# llrf_afe_dds_channel.net
KiCad netlist of a schematic drawn in Altium Designer
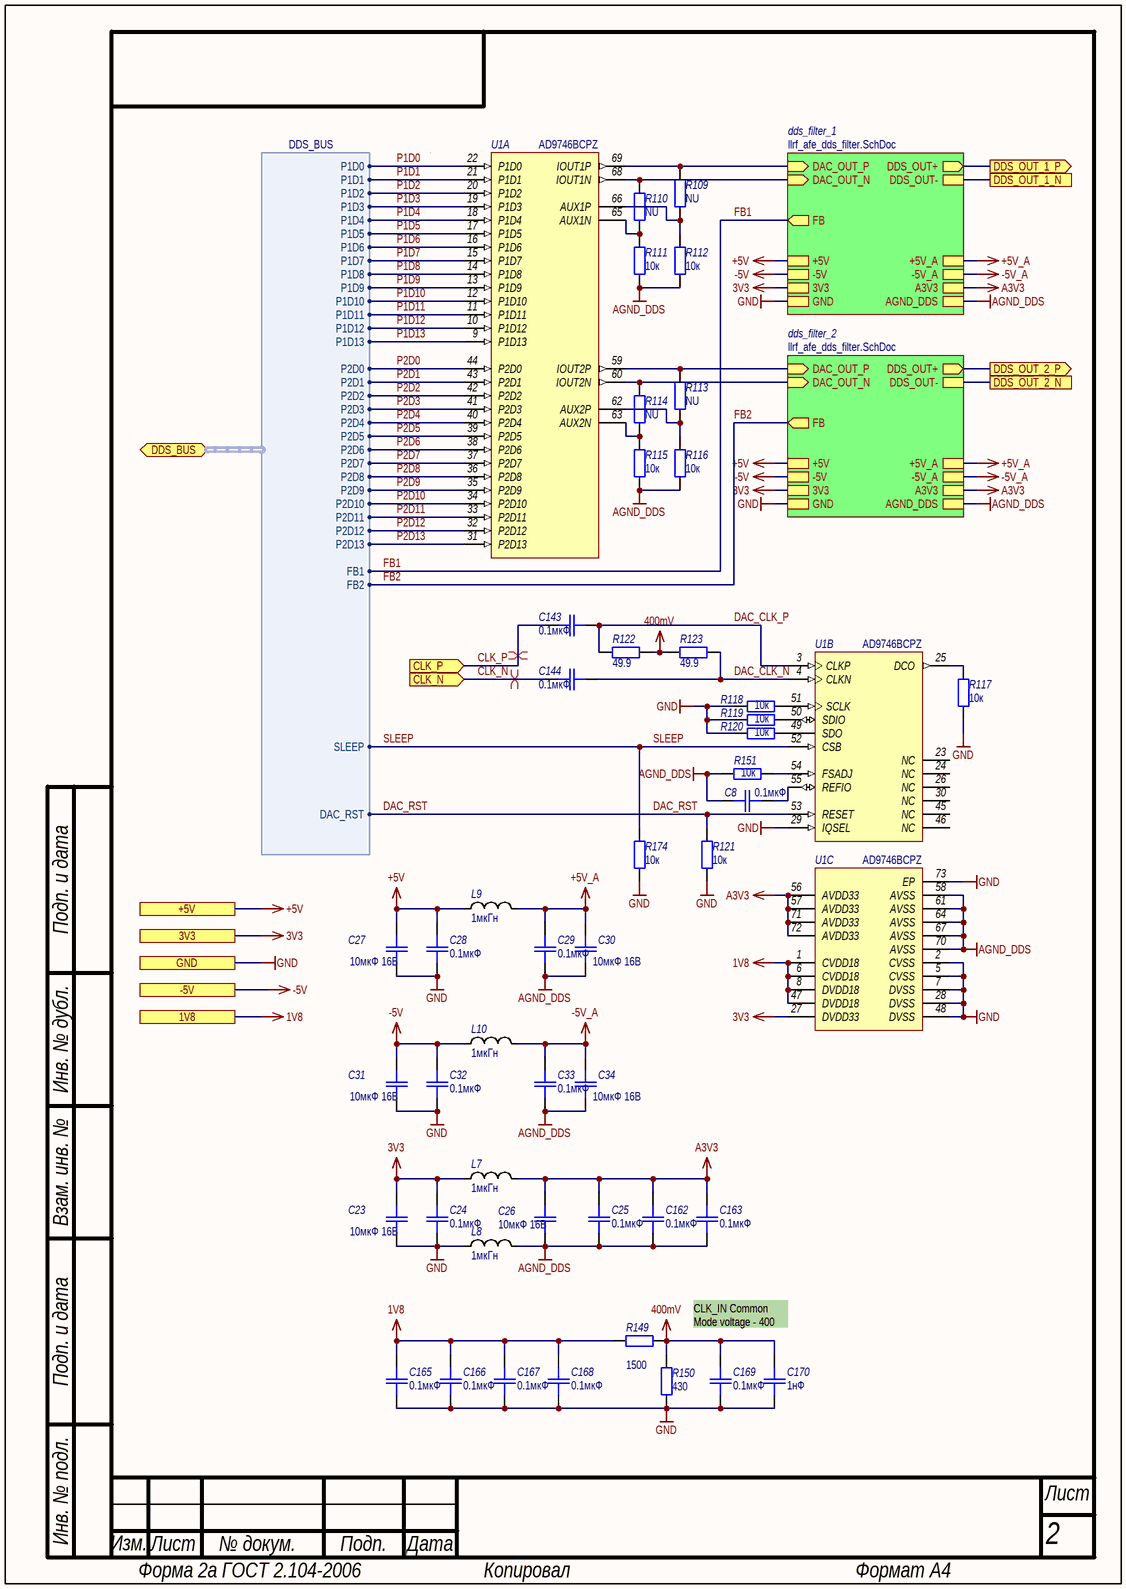
[diagram p0: llrf_afe_dds_channel.SchDoc]

(export (version "E")
  (design (tool "Eeschema 10.0.6"))
  (components
    (comp (ref "C8")
      (value "0.1мкФ")
      (footprint "SMD_C0402")
      (description "Capacitor")
      (libsource (lib "Passive") (part "Capacitor"))
    )
    (comp (ref "C23")
      (value "10мкФ 16В")
      (footprint "SMD_C0603")
      (description "Capacitor")
      (libsource (lib "Passive") (part "Capacitor"))
    )
    (comp (ref "C24")
      (value "0.1мкФ")
      (footprint "SMD_C0402")
      (description "Capacitor")
      (libsource (lib "Passive") (part "Capacitor"))
    )
    (comp (ref "C25")
      (value "0.1мкФ")
      (footprint "SMD_C0402")
      (description "Capacitor")
      (libsource (lib "Passive") (part "Capacitor"))
    )
    (comp (ref "C26")
      (value "10мкФ 16В")
      (footprint "SMD_C0603")
      (description "Capacitor")
      (libsource (lib "Passive") (part "Capacitor"))
    )
    (comp (ref "C27")
      (value "10мкФ 16В")
      (footprint "SMD_C0603")
      (description "Capacitor")
      (libsource (lib "Passive") (part "Capacitor"))
    )
    (comp (ref "C28")
      (value "0.1мкФ")
      (footprint "SMD_C0402")
      (description "Capacitor")
      (libsource (lib "Passive") (part "Capacitor"))
    )
    (comp (ref "C29")
      (value "0.1мкФ")
      (footprint "SMD_C0402")
      (description "Capacitor")
      (libsource (lib "Passive") (part "Capacitor"))
    )
    (comp (ref "C30")
      (value "10мкФ 16В")
      (footprint "SMD_C0603")
      (description "Capacitor")
      (libsource (lib "Passive") (part "Capacitor"))
    )
    (comp (ref "C31")
      (value "10мкФ 16В")
      (footprint "SMD_C0603")
      (description "Capacitor")
      (libsource (lib "Passive") (part "Capacitor"))
    )
    (comp (ref "C32")
      (value "0.1мкФ")
      (footprint "SMD_C0402")
      (description "Capacitor")
      (libsource (lib "Passive") (part "Capacitor"))
    )
    (comp (ref "C33")
      (value "0.1мкФ")
      (footprint "SMD_C0402")
      (description "Capacitor")
      (libsource (lib "Passive") (part "Capacitor"))
    )
    (comp (ref "C34")
      (value "10мкФ 16В")
      (footprint "SMD_C0603")
      (description "Capacitor")
      (libsource (lib "Passive") (part "Capacitor"))
    )
    (comp (ref "C143")
      (value "0.1мкФ")
      (footprint "SMD_C0402")
      (description "Capacitor")
      (libsource (lib "Passive") (part "Capacitor"))
    )
    (comp (ref "C144")
      (value "0.1мкФ")
      (footprint "SMD_C0402")
      (description "Capacitor")
      (libsource (lib "Passive") (part "Capacitor"))
    )
    (comp (ref "C162")
      (value "0.1мкФ")
      (footprint "SMD_C0402")
      (description "Capacitor")
      (libsource (lib "Passive") (part "Capacitor"))
    )
    (comp (ref "C163")
      (value "0.1мкФ")
      (footprint "SMD_C0402")
      (description "Capacitor")
      (libsource (lib "Passive") (part "Capacitor"))
    )
    (comp (ref "C165")
      (value "0.1мкФ")
      (footprint "SMD_C0402")
      (description "Capacitor")
      (libsource (lib "Passive") (part "Capacitor"))
    )
    (comp (ref "C166")
      (value "0.1мкФ")
      (footprint "SMD_C0402")
      (description "Capacitor")
      (libsource (lib "Passive") (part "Capacitor"))
    )
    (comp (ref "C167")
      (value "0.1мкФ")
      (footprint "SMD_C0402")
      (description "Capacitor")
      (libsource (lib "Passive") (part "Capacitor"))
    )
    (comp (ref "C168")
      (value "0.1мкФ")
      (footprint "SMD_C0402")
      (description "Capacitor")
      (libsource (lib "Passive") (part "Capacitor"))
    )
    (comp (ref "C169")
      (value "0.1мкФ")
      (footprint "SMD_C0402")
      (description "Capacitor")
      (libsource (lib "Passive") (part "Capacitor"))
    )
    (comp (ref "C170")
      (value "1нФ")
      (footprint "SMD_C0402")
      (description "Capacitor")
      (libsource (lib "Passive") (part "Capacitor"))
    )
    (comp (ref "L7")
      (value "1мкГн")
      (footprint "SMD_0805")
      (description "Inductor")
      (libsource (lib "Passive") (part "Inductor"))
    )
    (comp (ref "L8")
      (value "1мкГн")
      (footprint "SMD_0805")
      (description "Inductor")
      (libsource (lib "Passive") (part "Inductor"))
    )
    (comp (ref "L9")
      (value "1мкГн")
      (footprint "SMD_0805")
      (description "Inductor")
      (libsource (lib "Passive") (part "Inductor"))
    )
    (comp (ref "L10")
      (value "1мкГн")
      (footprint "SMD_0805")
      (description "Inductor")
      (libsource (lib "Passive") (part "Inductor"))
    )
    (comp (ref "R109")
      (value "NU")
      (footprint "SMD_0603")
      (description "Resistor")
      (libsource (lib "") (part "Resistor_1"))
    )
    (comp (ref "R110")
      (value "NU")
      (footprint "SMD_0603")
      (description "Resistor")
      (libsource (lib "") (part "Resistor_1"))
    )
    (comp (ref "R111")
      (value "10к")
      (footprint "SMD_0603")
      (description "Resistor")
      (libsource (lib "") (part "Resistor_1"))
    )
    (comp (ref "R112")
      (value "10к")
      (footprint "SMD_0603")
      (description "Resistor")
      (libsource (lib "") (part "Resistor_1"))
    )
    (comp (ref "R113")
      (value "NU")
      (footprint "SMD_0603")
      (description "Resistor")
      (libsource (lib "") (part "Resistor_1"))
    )
    (comp (ref "R114")
      (value "NU")
      (footprint "SMD_0603")
      (description "Resistor")
      (libsource (lib "") (part "Resistor_1"))
    )
    (comp (ref "R115")
      (value "10к")
      (footprint "SMD_0603")
      (description "Resistor")
      (libsource (lib "") (part "Resistor_1"))
    )
    (comp (ref "R116")
      (value "10к")
      (footprint "SMD_0603")
      (description "Resistor")
      (libsource (lib "") (part "Resistor_1"))
    )
    (comp (ref "R117")
      (value "10к")
      (footprint "SMD_0603")
      (description "Resistor")
      (libsource (lib "Passive") (part "Resistor"))
    )
    (comp (ref "R118")
      (value "10к")
      (footprint "SMD_0603")
      (description "Resistor")
      (libsource (lib "") (part "Resistor_2"))
    )
    (comp (ref "R119")
      (value "10к")
      (footprint "SMD_0603")
      (description "Resistor")
      (libsource (lib "") (part "Resistor_2"))
    )
    (comp (ref "R120")
      (value "10к")
      (footprint "SMD_0603")
      (description "Resistor")
      (libsource (lib "") (part "Resistor_2"))
    )
    (comp (ref "R121")
      (value "10к")
      (footprint "SMD_0603")
      (description "Resistor")
      (libsource (lib "Passive") (part "Resistor"))
    )
    (comp (ref "R122")
      (value "49.9")
      (footprint "SMD_0603")
      (description "Resistor")
      (libsource (lib "") (part "Resistor_3"))
    )
    (comp (ref "R123")
      (value "49.9")
      (footprint "SMD_0603")
      (description "Resistor")
      (libsource (lib "") (part "Resistor_3"))
    )
    (comp (ref "R149")
      (value "1500")
      (footprint "SMD_0603")
      (description "Resistor")
      (libsource (lib "") (part "Resistor_3"))
    )
    (comp (ref "R150")
      (value "430")
      (footprint "SMD_0603")
      (description "Resistor")
      (libsource (lib "") (part "Resistor_1"))
    )
    (comp (ref "R151")
      (value "10к")
      (footprint "SMD_0603")
      (description "Resistor")
      (libsource (lib "") (part "Resistor_1"))
    )
    (comp (ref "R174")
      (value "10к")
      (footprint "SMD_0603")
      (description "Resistor")
      (libsource (lib "Passive") (part "Resistor"))
    )
    (comp (ref "U1")
      (value "AD9746BCPZ")
      (footprint "LFCSP-72")
      (description "Dual 14-Bit Digital-to-Analog Converter, 250 Msps, -40 to +85 degC, CP-72-1, Pb-Free, Tray")
      (fields (field (name "НАИМЕНОВАНИЕ") "AD9746BCPZ"))
      (libsource (lib "Dac") (part "AD9746BCPZ"))
    )
  )
  (nets
    (net (code "2") (name "+5V") (class "Default")
      (node (ref "C27") (pin "2") (pinfunction "2_2") (pintype "passive"))
      (node (ref "C28") (pin "2") (pinfunction "2_2") (pintype "passive"))
      (node (ref "L9") (pin "1") (pinfunction "1_1") (pintype "passive"))
    )
    (net (code "3") (name "+5V_A") (class "Default")
      (node (ref "C29") (pin "2") (pinfunction "2_2") (pintype "passive"))
      (node (ref "C30") (pin "2") (pinfunction "2_2") (pintype "passive"))
      (node (ref "L9") (pin "2") (pinfunction "2_2") (pintype "passive"))
    )
    (net (code "4") (name "-5V") (class "Default")
      (node (ref "C31") (pin "2") (pinfunction "2_2") (pintype "passive"))
      (node (ref "C32") (pin "2") (pinfunction "2_2") (pintype "passive"))
      (node (ref "L10") (pin "1") (pinfunction "1_1") (pintype "passive"))
    )
    (net (code "5") (name "-5V_A") (class "Default")
      (node (ref "C33") (pin "2") (pinfunction "2_2") (pintype "passive"))
      (node (ref "C34") (pin "2") (pinfunction "2_2") (pintype "passive"))
      (node (ref "L10") (pin "2") (pinfunction "2_2") (pintype "passive"))
    )
    (net (code "6") (name "/CLK_N") (class "Default")
      (node (ref "C144") (pin "2") (pinfunction "2_2") (pintype "passive"))
    )
    (net (code "7") (name "/CLK_P") (class "Default")
      (node (ref "C143") (pin "2") (pinfunction "2_2") (pintype "passive"))
    )
    (net (code "8") (name "/DAC_CLK_N") (class "Default")
      (node (ref "C144") (pin "1") (pinfunction "1_1") (pintype "passive"))
      (node (ref "R123") (pin "1") (pinfunction "1_1") (pintype "passive"))
      (node (ref "U1") (pin "4") (pinfunction "CLKN_4") (pintype "input"))
    )
    (net (code "9") (name "/DAC_CLK_P") (class "Default")
      (node (ref "C143") (pin "1") (pinfunction "1_1") (pintype "passive"))
      (node (ref "R122") (pin "2") (pinfunction "2_2") (pintype "passive"))
      (node (ref "U1") (pin "3") (pinfunction "CLKP_3") (pintype "input"))
    )
    (net (code "10") (name "/DAC_OUT_N") (class "Default")
      (node (ref "R110") (pin "2") (pinfunction "2_2") (pintype "passive"))
      (node (ref "U1") (pin "68") (pinfunction "IOUT1N_68") (pintype "output"))
    )
    (net (code "11") (name "/DAC_OUT_N_1") (class "Default")
      (node (ref "R114") (pin "2") (pinfunction "2_2") (pintype "passive"))
      (node (ref "U1") (pin "60") (pinfunction "IOUT2N_60") (pintype "output"))
    )
    (net (code "12") (name "/DAC_OUT_P") (class "Default")
      (node (ref "R109") (pin "2") (pinfunction "2_2") (pintype "passive"))
      (node (ref "U1") (pin "69") (pinfunction "IOUT1P_69") (pintype "output"))
    )
    (net (code "13") (name "/DAC_OUT_P_1") (class "Default")
      (node (ref "R113") (pin "2") (pinfunction "2_2") (pintype "passive"))
      (node (ref "U1") (pin "59") (pinfunction "IOUT2P_59") (pintype "output"))
    )
    (net (code "14") (name "/DAC_RST") (class "Default")
      (node (ref "R121") (pin "2") (pinfunction "2_2") (pintype "passive"))
      (node (ref "U1") (pin "53") (pinfunction "RESET_53") (pintype "input"))
    )
    (net (code "21") (name "/P1D0") (class "Default")
      (node (ref "U1") (pin "22") (pinfunction "P1D0_22") (pintype "input"))
    )
    (net (code "22") (name "/P1D1") (class "Default")
      (node (ref "U1") (pin "21") (pinfunction "P1D1_21") (pintype "input"))
    )
    (net (code "23") (name "/P1D2") (class "Default")
      (node (ref "U1") (pin "20") (pinfunction "P1D2_20") (pintype "input"))
    )
    (net (code "24") (name "/P1D3") (class "Default")
      (node (ref "U1") (pin "19") (pinfunction "P1D3_19") (pintype "input"))
    )
    (net (code "25") (name "/P1D4") (class "Default")
      (node (ref "U1") (pin "18") (pinfunction "P1D4_18") (pintype "input"))
    )
    (net (code "26") (name "/P1D5") (class "Default")
      (node (ref "U1") (pin "17") (pinfunction "P1D5_17") (pintype "input"))
    )
    (net (code "27") (name "/P1D6") (class "Default")
      (node (ref "U1") (pin "16") (pinfunction "P1D6_16") (pintype "input"))
    )
    (net (code "28") (name "/P1D7") (class "Default")
      (node (ref "U1") (pin "15") (pinfunction "P1D7_15") (pintype "input"))
    )
    (net (code "29") (name "/P1D8") (class "Default")
      (node (ref "U1") (pin "14") (pinfunction "P1D8_14") (pintype "input"))
    )
    (net (code "30") (name "/P1D9") (class "Default")
      (node (ref "U1") (pin "13") (pinfunction "P1D9_13") (pintype "input"))
    )
    (net (code "31") (name "/P1D10") (class "Default")
      (node (ref "U1") (pin "12") (pinfunction "P1D10_12") (pintype "input"))
    )
    (net (code "32") (name "/P1D11") (class "Default")
      (node (ref "U1") (pin "11") (pinfunction "P1D11_11") (pintype "input"))
    )
    (net (code "33") (name "/P1D12") (class "Default")
      (node (ref "U1") (pin "10") (pinfunction "P1D12_10") (pintype "input"))
    )
    (net (code "34") (name "/P1D13") (class "Default")
      (node (ref "U1") (pin "9") (pinfunction "P1D13_9") (pintype "input"))
    )
    (net (code "35") (name "/P2D0") (class "Default")
      (node (ref "U1") (pin "44") (pinfunction "P2D0_44") (pintype "input"))
    )
    (net (code "36") (name "/P2D1") (class "Default")
      (node (ref "U1") (pin "43") (pinfunction "P2D1_43") (pintype "input"))
    )
    (net (code "37") (name "/P2D2") (class "Default")
      (node (ref "U1") (pin "42") (pinfunction "P2D2_42") (pintype "input"))
    )
    (net (code "38") (name "/P2D3") (class "Default")
      (node (ref "U1") (pin "41") (pinfunction "P2D3_41") (pintype "input"))
    )
    (net (code "39") (name "/P2D4") (class "Default")
      (node (ref "U1") (pin "40") (pinfunction "P2D4_40") (pintype "input"))
    )
    (net (code "40") (name "/P2D5") (class "Default")
      (node (ref "U1") (pin "39") (pinfunction "P2D5_39") (pintype "input"))
    )
    (net (code "41") (name "/P2D6") (class "Default")
      (node (ref "U1") (pin "38") (pinfunction "P2D6_38") (pintype "input"))
    )
    (net (code "42") (name "/P2D7") (class "Default")
      (node (ref "U1") (pin "37") (pinfunction "P2D7_37") (pintype "input"))
    )
    (net (code "43") (name "/P2D8") (class "Default")
      (node (ref "U1") (pin "36") (pinfunction "P2D8_36") (pintype "input"))
    )
    (net (code "44") (name "/P2D9") (class "Default")
      (node (ref "U1") (pin "35") (pinfunction "P2D9_35") (pintype "input"))
    )
    (net (code "45") (name "/P2D10") (class "Default")
      (node (ref "U1") (pin "34") (pinfunction "P2D10_34") (pintype "input"))
    )
    (net (code "46") (name "/P2D11") (class "Default")
      (node (ref "U1") (pin "33") (pinfunction "P2D11_33") (pintype "input"))
    )
    (net (code "47") (name "/P2D12") (class "Default")
      (node (ref "U1") (pin "32") (pinfunction "P2D12_32") (pintype "input"))
    )
    (net (code "48") (name "/P2D13") (class "Default")
      (node (ref "U1") (pin "31") (pinfunction "P2D13_31") (pintype "input"))
    )
    (net (code "49") (name "/SLEEP") (class "Default")
      (node (ref "R174") (pin "2") (pinfunction "2_2") (pintype "passive"))
      (node (ref "U1") (pin "52") (pinfunction "CSB_52") (pintype "input"))
    )
    (net (code "51") (name "1V8") (class "Default")
      (node (ref "C165") (pin "2") (pinfunction "2_2") (pintype "passive"))
      (node (ref "C166") (pin "2") (pinfunction "2_2") (pintype "passive"))
      (node (ref "C167") (pin "2") (pinfunction "2_2") (pintype "passive"))
      (node (ref "C168") (pin "2") (pinfunction "2_2") (pintype "passive"))
      (node (ref "R149") (pin "2") (pinfunction "2_2") (pintype "passive"))
      (node (ref "U1") (pin "1") (pinfunction "CVDD18_1") (pintype "power_in"))
      (node (ref "U1") (pin "47") (pinfunction "DVDD18_47") (pintype "power_in"))
      (node (ref "U1") (pin "6") (pinfunction "CVDD18_6") (pintype "power_in"))
      (node (ref "U1") (pin "8") (pinfunction "DVDD18_8") (pintype "power_in"))
    )
    (net (code "52") (name "3V3") (class "Default")
      (node (ref "C23") (pin "2") (pinfunction "2_2") (pintype "passive"))
      (node (ref "C24") (pin "2") (pinfunction "2_2") (pintype "passive"))
      (node (ref "L7") (pin "1") (pinfunction "1_1") (pintype "passive"))
      (node (ref "U1") (pin "27") (pinfunction "DVDD33_27") (pintype "power_in"))
    )
    (net (code "53") (name "400mV") (class "Default")
      (node (ref "C169") (pin "1") (pinfunction "1_1") (pintype "passive"))
      (node (ref "C170") (pin "1") (pinfunction "1_1") (pintype "passive"))
      (node (ref "R122") (pin "1") (pinfunction "1_1") (pintype "passive"))
      (node (ref "R123") (pin "2") (pinfunction "2_2") (pintype "passive"))
      (node (ref "R149") (pin "1") (pinfunction "1_1") (pintype "passive"))
      (node (ref "R150") (pin "2") (pinfunction "2_2") (pintype "passive"))
    )
    (net (code "54") (name "A3V3") (class "Default")
      (node (ref "C162") (pin "2") (pinfunction "2_2") (pintype "passive"))
      (node (ref "C163") (pin "2") (pinfunction "2_2") (pintype "passive"))
      (node (ref "C25") (pin "2") (pinfunction "2_2") (pintype "passive"))
      (node (ref "C26") (pin "2") (pinfunction "2_2") (pintype "passive"))
      (node (ref "L7") (pin "2") (pinfunction "2_2") (pintype "passive"))
      (node (ref "U1") (pin "56") (pinfunction "AVDD33_56") (pintype "power_in"))
      (node (ref "U1") (pin "57") (pinfunction "AVDD33_57") (pintype "power_in"))
      (node (ref "U1") (pin "71") (pinfunction "AVDD33_71") (pintype "power_in"))
      (node (ref "U1") (pin "72") (pinfunction "AVDD33_72") (pintype "power_in"))
    )
    (net (code "55") (name "AGND_DDS") (class "Default")
      (node (ref "C162") (pin "1") (pinfunction "1_1") (pintype "passive"))
      (node (ref "C163") (pin "1") (pinfunction "1_1") (pintype "passive"))
      (node (ref "C25") (pin "1") (pinfunction "1_1") (pintype "passive"))
      (node (ref "C26") (pin "1") (pinfunction "1_1") (pintype "passive"))
      (node (ref "C29") (pin "1") (pinfunction "1_1") (pintype "passive"))
      (node (ref "C30") (pin "1") (pinfunction "1_1") (pintype "passive"))
      (node (ref "C33") (pin "1") (pinfunction "1_1") (pintype "passive"))
      (node (ref "C34") (pin "1") (pinfunction "1_1") (pintype "passive"))
      (node (ref "C8") (pin "1") (pinfunction "1_1") (pintype "passive"))
      (node (ref "L8") (pin "2") (pinfunction "2_2") (pintype "passive"))
      (node (ref "R111") (pin "1") (pinfunction "1_1") (pintype "passive"))
      (node (ref "R112") (pin "1") (pinfunction "1_1") (pintype "passive"))
      (node (ref "R115") (pin "1") (pinfunction "1_1") (pintype "passive"))
      (node (ref "R116") (pin "1") (pinfunction "1_1") (pintype "passive"))
      (node (ref "R151") (pin "1") (pinfunction "1_1") (pintype "passive"))
      (node (ref "U1") (pin "58") (pinfunction "AVSS_58") (pintype "power_in"))
      (node (ref "U1") (pin "61") (pinfunction "AVSS_61") (pintype "power_in"))
      (node (ref "U1") (pin "64") (pinfunction "AVSS_64") (pintype "power_in"))
      (node (ref "U1") (pin "67") (pinfunction "AVSS_67") (pintype "power_in"))
      (node (ref "U1") (pin "70") (pinfunction "AVSS_70") (pintype "power_in"))
    )
    (net (code "56") (name "GND") (class "Default")
      (node (ref "C165") (pin "1") (pinfunction "1_1") (pintype "passive"))
      (node (ref "C166") (pin "1") (pinfunction "1_1") (pintype "passive"))
      (node (ref "C167") (pin "1") (pinfunction "1_1") (pintype "passive"))
      (node (ref "C168") (pin "1") (pinfunction "1_1") (pintype "passive"))
      (node (ref "C169") (pin "2") (pinfunction "2_2") (pintype "passive"))
      (node (ref "C170") (pin "2") (pinfunction "2_2") (pintype "passive"))
      (node (ref "C23") (pin "1") (pinfunction "1_1") (pintype "passive"))
      (node (ref "C24") (pin "1") (pinfunction "1_1") (pintype "passive"))
      (node (ref "C27") (pin "1") (pinfunction "1_1") (pintype "passive"))
      (node (ref "C28") (pin "1") (pinfunction "1_1") (pintype "passive"))
      (node (ref "C31") (pin "1") (pinfunction "1_1") (pintype "passive"))
      (node (ref "C32") (pin "1") (pinfunction "1_1") (pintype "passive"))
      (node (ref "L8") (pin "1") (pinfunction "1_1") (pintype "passive"))
      (node (ref "R117") (pin "1") (pinfunction "1_1") (pintype "passive"))
      (node (ref "R118") (pin "2") (pinfunction "2_2") (pintype "passive"))
      (node (ref "R119") (pin "2") (pinfunction "2_2") (pintype "passive"))
      (node (ref "R120") (pin "2") (pinfunction "2_2") (pintype "passive"))
      (node (ref "R121") (pin "1") (pinfunction "1_1") (pintype "passive"))
      (node (ref "R150") (pin "1") (pinfunction "1_1") (pintype "passive"))
      (node (ref "R174") (pin "1") (pinfunction "1_1") (pintype "passive"))
      (node (ref "U1") (pin "2") (pinfunction "CVSS_2") (pintype "power_in"))
      (node (ref "U1") (pin "28") (pinfunction "DVSS_28") (pintype "power_in"))
      (node (ref "U1") (pin "29") (pinfunction "IQSEL_29") (pintype "input"))
      (node (ref "U1") (pin "48") (pinfunction "DVSS_48") (pintype "power_in"))
      (node (ref "U1") (pin "5") (pinfunction "CVSS_5") (pintype "power_in"))
      (node (ref "U1") (pin "7") (pinfunction "DVSS_7") (pintype "power_in"))
      (node (ref "U1") (pin "73") (pinfunction "EP_73") (pintype "power_in"))
    )
    (net (code "57") (name "Net-(U1A-AUX1N)") (class "Default")
      (node (ref "R110") (pin "1") (pinfunction "1_1") (pintype "passive"))
      (node (ref "R111") (pin "2") (pinfunction "2_2") (pintype "passive"))
      (node (ref "U1") (pin "65") (pinfunction "AUX1N_65") (pintype "tri_state"))
    )
    (net (code "58") (name "Net-(U1A-AUX1P)") (class "Default")
      (node (ref "R109") (pin "1") (pinfunction "1_1") (pintype "passive"))
      (node (ref "R112") (pin "2") (pinfunction "2_2") (pintype "passive"))
      (node (ref "U1") (pin "66") (pinfunction "AUX1P_66") (pintype "tri_state"))
    )
    (net (code "59") (name "Net-(U1A-AUX2N)") (class "Default")
      (node (ref "R114") (pin "1") (pinfunction "1_1") (pintype "passive"))
      (node (ref "R115") (pin "2") (pinfunction "2_2") (pintype "passive"))
      (node (ref "U1") (pin "63") (pinfunction "AUX2N_63") (pintype "tri_state"))
    )
    (net (code "60") (name "Net-(U1A-AUX2P)") (class "Default")
      (node (ref "R113") (pin "1") (pinfunction "1_1") (pintype "passive"))
      (node (ref "R116") (pin "2") (pinfunction "2_2") (pintype "passive"))
      (node (ref "U1") (pin "62") (pinfunction "AUX2P_62") (pintype "tri_state"))
    )
    (net (code "61") (name "Net-(U1B-DCO)") (class "Default")
      (node (ref "R117") (pin "2") (pinfunction "2_2") (pintype "passive"))
      (node (ref "U1") (pin "25") (pinfunction "DCO_25") (pintype "output"))
    )
    (net (code "62") (name "Net-(U1B-FSADJ)") (class "Default")
      (node (ref "R151") (pin "2") (pinfunction "2_2") (pintype "passive"))
      (node (ref "U1") (pin "54") (pinfunction "FSADJ_54") (pintype "input"))
    )
    (net (code "63") (name "Net-(U1B-REFIO)") (class "Default")
      (node (ref "C8") (pin "2") (pinfunction "2_2") (pintype "passive"))
      (node (ref "U1") (pin "55") (pinfunction "REFIO_55") (pintype "bidirectional"))
    )
    (net (code "64") (name "Net-(U1B-SCLK)") (class "Default")
      (node (ref "R118") (pin "1") (pinfunction "1_1") (pintype "passive"))
      (node (ref "U1") (pin "51") (pinfunction "SCLK_51") (pintype "input"))
    )
    (net (code "65") (name "Net-(U1B-SDIO)") (class "Default")
      (node (ref "R119") (pin "1") (pinfunction "1_1") (pintype "passive"))
      (node (ref "U1") (pin "50") (pinfunction "SDIO_50") (pintype "bidirectional"))
    )
    (net (code "66") (name "Net-(U1B-SDO)") (class "Default")
      (node (ref "R120") (pin "1") (pinfunction "1_1") (pintype "passive"))
      (node (ref "U1") (pin "49") (pinfunction "SDO_49") (pintype "tri_state"))
    )
    (net (code "67") (name "unconnected-(U1B-NC-Pad23)") (class "Default")
      (node (ref "U1") (pin "23") (pinfunction "NC_23") (pintype "passive"))
    )
    (net (code "68") (name "unconnected-(U1B-NC-Pad24)") (class "Default")
      (node (ref "U1") (pin "24") (pinfunction "NC_24") (pintype "passive"))
    )
    (net (code "69") (name "unconnected-(U1B-NC-Pad26)") (class "Default")
      (node (ref "U1") (pin "26") (pinfunction "NC_26") (pintype "passive"))
    )
    (net (code "70") (name "unconnected-(U1B-NC-Pad30)") (class "Default")
      (node (ref "U1") (pin "30") (pinfunction "NC_30") (pintype "passive"))
    )
    (net (code "71") (name "unconnected-(U1B-NC-Pad45)") (class "Default")
      (node (ref "U1") (pin "45") (pinfunction "NC_45") (pintype "passive"))
    )
    (net (code "72") (name "unconnected-(U1B-NC-Pad46)") (class "Default")
      (node (ref "U1") (pin "46") (pinfunction "NC_46") (pintype "passive"))
    )
  )
)
